# PaxInstrument-T400.net
KiCad netlist of a schematic drawn in EAGLE
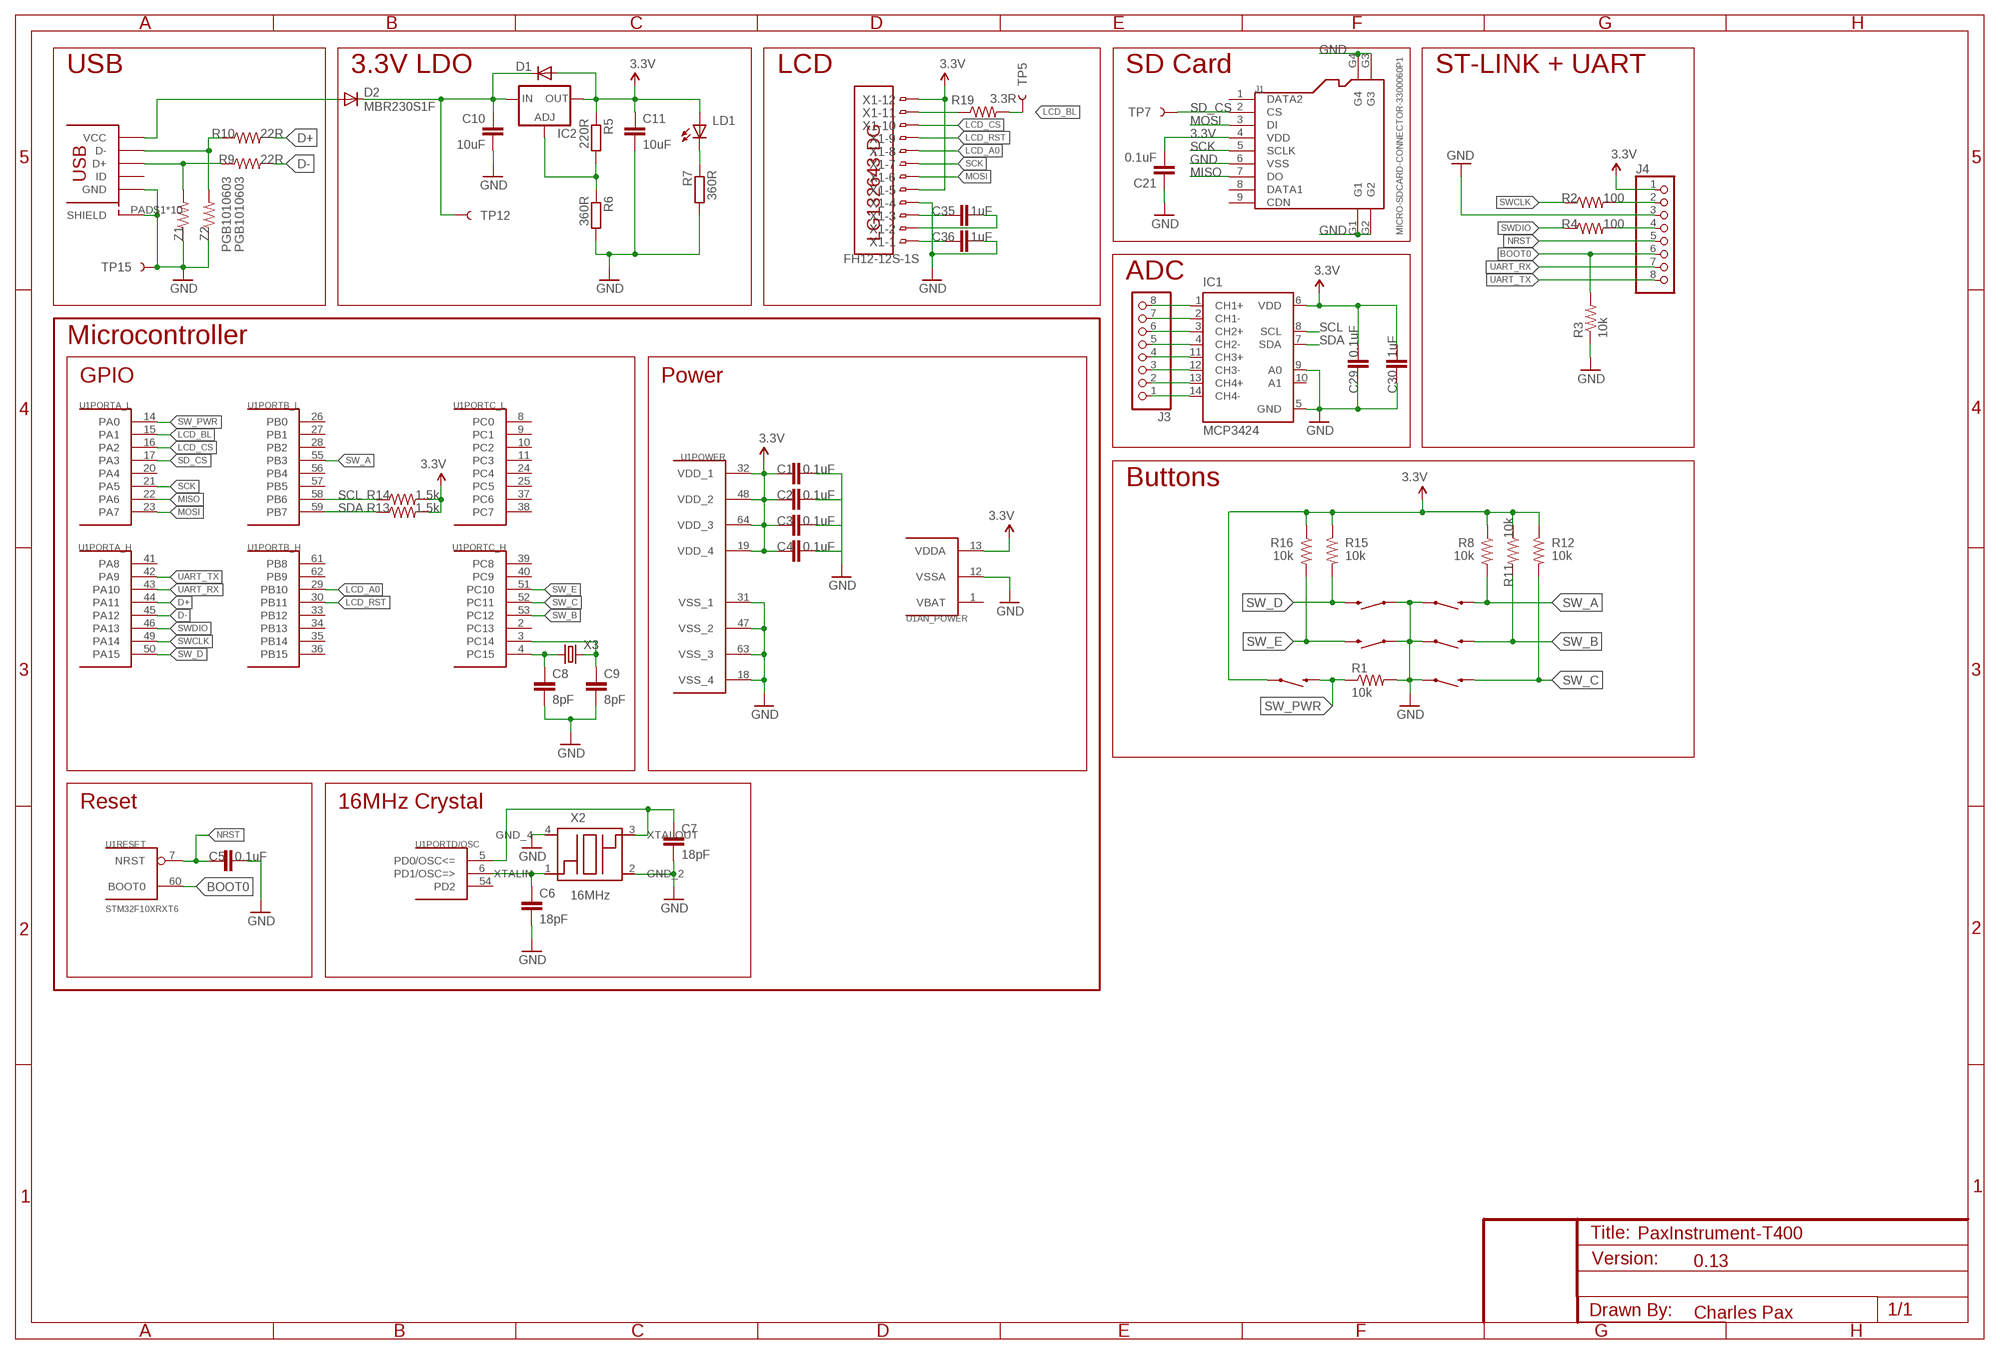
[diagram p0: schematic, sheet 1]

(export (version "E")
  (design (tool "Eeschema 10.0.6"))
  (components
    (comp (ref "C1")
      (value "0.1uF")
      (footprint "eagle-import:SPARKFUN-CAPACITORS_0603-CAP")
      (libsource (lib "eagle-import") (part "SPARKFUN-CAPACITORS_CAP0603-CAP"))
    )
    (comp (ref "C2")
      (value "0.1uF")
      (footprint "eagle-import:SPARKFUN-CAPACITORS_0603-CAP")
      (libsource (lib "eagle-import") (part "SPARKFUN-CAPACITORS_CAP0603-CAP"))
    )
    (comp (ref "C3")
      (value "0.1uF")
      (footprint "eagle-import:SPARKFUN-CAPACITORS_0603-CAP")
      (libsource (lib "eagle-import") (part "SPARKFUN-CAPACITORS_CAP0603-CAP"))
    )
    (comp (ref "C4")
      (value "0.1uF")
      (footprint "eagle-import:SPARKFUN-CAPACITORS_0603-CAP")
      (libsource (lib "eagle-import") (part "SPARKFUN-CAPACITORS_CAP0603-CAP"))
    )
    (comp (ref "C5")
      (value "0.1uF")
      (footprint "eagle-import:SPARKFUN-CAPACITORS_0603-CAP")
      (libsource (lib "eagle-import") (part "SPARKFUN-CAPACITORS_CAP0603-CAP"))
    )
    (comp (ref "C6")
      (value "18pF")
      (footprint "eagle-import:SPARKFUN-CAPACITORS_0603-CAP")
      (libsource (lib "eagle-import") (part "SPARKFUN-CAPACITORS_CAP0603-CAP"))
    )
    (comp (ref "C7")
      (value "18pF")
      (footprint "eagle-import:SPARKFUN-CAPACITORS_0603-CAP")
      (libsource (lib "eagle-import") (part "SPARKFUN-CAPACITORS_CAP0603-CAP"))
    )
    (comp (ref "C8")
      (value "8pF")
      (footprint "eagle-import:SPARKFUN-CAPACITORS_0603-CAP")
      (libsource (lib "eagle-import") (part "SPARKFUN-CAPACITORS_CAP0603-CAP"))
    )
    (comp (ref "C9")
      (value "8pF")
      (footprint "eagle-import:SPARKFUN-CAPACITORS_0603-CAP")
      (libsource (lib "eagle-import") (part "SPARKFUN-CAPACITORS_CAP0603-CAP"))
    )
    (comp (ref "C10")
      (value "10uF")
      (footprint "eagle-import:0603")
      (libsource (lib "eagle-import") (part "C0603"))
    )
    (comp (ref "C11")
      (value "10uF")
      (footprint "eagle-import:0603")
      (libsource (lib "eagle-import") (part "C0603"))
    )
    (comp (ref "C21")
      (value "0.1uF")
      (footprint "eagle-import:SPARKFUN-CAPACITORS_0603-CAP")
      (libsource (lib "eagle-import") (part "SPARKFUN-CAPACITORS_CAP0603-CAP"))
    )
    (comp (ref "C29")
      (value "0.1uF")
      (footprint "eagle-import:SPARKFUN-CAPACITORS_0603-CAP")
      (libsource (lib "eagle-import") (part "SPARKFUN-CAPACITORS_CAP0603-CAP"))
    )
    (comp (ref "C30")
      (value "1uF")
      (footprint "eagle-import:SPARKFUN-CAPACITORS_0603-CAP")
      (libsource (lib "eagle-import") (part "SPARKFUN-CAPACITORS_CAP0603-CAP"))
    )
    (comp (ref "C35")
      (value "1uF")
      (footprint "eagle-import:SPARKFUN-CAPACITORS_0603-CAP")
      (libsource (lib "eagle-import") (part "SPARKFUN-CAPACITORS_CAP0603-CAP"))
    )
    (comp (ref "C36")
      (value "1uF")
      (footprint "eagle-import:SPARKFUN-CAPACITORS_0603-CAP")
      (libsource (lib "eagle-import") (part "SPARKFUN-CAPACITORS_CAP0603-CAP"))
    )
    (comp (ref "D1")
      (value "1N4148W")
      (footprint "eagle-import:SOD-123_MINI-SMA")
      (libsource (lib "eagle-import") (part "CGRM400-G1"))
    )
    (comp (ref "D2")
      (value "MBR230S1F")
      (footprint "eagle-import:SOD123")
      (fields (field (name "MF") "DIODES INC") (field (name "MPN") "MBR230S1F-7"))
      (libsource (lib "eagle-import") (part "SPARKFUN-DISCRETESEMI_DIODESOD123SOD123"))
    )
    (comp (ref "IC1")
      (value "MCP3424")
      (footprint "eagle-import:SO14")
      (fields (field (name "MF") "Microchip Technology") (field (name "MPN") "MCP3424-E/SL"))
      (libsource (lib "eagle-import") (part "MCP3424"))
    )
    (comp (ref "IC2")
      (value "LM317AEMP")
      (footprint "eagle-import:SOT223")
      (libsource (lib "eagle-import") (part "LM317?MSTT3"))
    )
    (comp (ref "J1")
      (value "MICRO-SDCARD-CONNECTOR-3300060P1")
      (footprint "eagle-import:9P-SMD-W-RING")
      (fields (field (name "MF") "SUNTECH") (field (name "MPN") "ST-TF-003A"))
      (libsource (lib "eagle-import") (part "MICRO-SDCARD-CONNECTOR-3300060P1"))
    )
    (comp (ref "J2")
      (value "USB_MICROSMT+THRUHULE")
      (footprint "eagle-import:USB_MICRO_THRUHOLE")
      (fields (field (name "MF") "FCI") (field (name "MPN") "10118194-0001LF"))
      (libsource (lib "eagle-import") (part "USB_MICROSMT+THRUHULE"))
    )
    (comp (ref "J3")
      (value "PINHD-1X8")
      (footprint "eagle-import:1X08")
      (libsource (lib "eagle-import") (part "PINHD-1X8"))
    )
    (comp (ref "J4")
      (value "PINHD-1X8")
      (footprint "eagle-import:1X08")
      (libsource (lib "eagle-import") (part "PINHD-1X8"))
    )
    (comp (ref "LD1")
      (value "LEDCHIPLED_0805")
      (footprint "eagle-import:CHIPLED_0805")
      (libsource (lib "eagle-import") (part "LEDCHIPLED_0805"))
    )
    (comp (ref "R1")
      (value "10k")
      (footprint "eagle-import:SPARKFUN-RESISTORS_0603-RES")
      (libsource (lib "eagle-import") (part "SPARKFUN-RESISTORS_RESISTOR0603-RES"))
    )
    (comp (ref "R2")
      (value "100")
      (footprint "eagle-import:SPARKFUN-RESISTORS_0603-RES")
      (libsource (lib "eagle-import") (part "SPARKFUN-RESISTORS_RESISTOR0603-RES"))
    )
    (comp (ref "R3")
      (value "10k")
      (footprint "eagle-import:SPARKFUN-RESISTORS_0603-RES")
      (libsource (lib "eagle-import") (part "SPARKFUN-RESISTORS_RESISTOR0603-RES"))
    )
    (comp (ref "R4")
      (value "100")
      (footprint "eagle-import:SPARKFUN-RESISTORS_0603-RES")
      (libsource (lib "eagle-import") (part "SPARKFUN-RESISTORS_RESISTOR0603-RES"))
    )
    (comp (ref "R5")
      (value "220R")
      (footprint "eagle-import:0603")
      (libsource (lib "eagle-import") (part "R0603"))
    )
    (comp (ref "R6")
      (value "360R")
      (footprint "eagle-import:0603")
      (libsource (lib "eagle-import") (part "R0603"))
    )
    (comp (ref "R7")
      (value "360R")
      (footprint "eagle-import:0603")
      (libsource (lib "eagle-import") (part "R0603"))
    )
    (comp (ref "R8")
      (value "10k")
      (footprint "eagle-import:SPARKFUN-RESISTORS_0603-RES")
      (libsource (lib "eagle-import") (part "SPARKFUN-RESISTORS_RESISTOR0603-RES"))
    )
    (comp (ref "R9")
      (value "22R")
      (footprint "eagle-import:SPARKFUN-RESISTORS_0603-RES")
      (libsource (lib "eagle-import") (part "SPARKFUN-RESISTORS_RESISTOR0603-RES"))
    )
    (comp (ref "R10")
      (value "22R")
      (footprint "eagle-import:SPARKFUN-RESISTORS_0603-RES")
      (libsource (lib "eagle-import") (part "SPARKFUN-RESISTORS_RESISTOR0603-RES"))
    )
    (comp (ref "R11")
      (value "10k")
      (footprint "eagle-import:SPARKFUN-RESISTORS_0603-RES")
      (libsource (lib "eagle-import") (part "SPARKFUN-RESISTORS_RESISTOR0603-RES"))
    )
    (comp (ref "R12")
      (value "10k")
      (footprint "eagle-import:SPARKFUN-RESISTORS_0603-RES")
      (libsource (lib "eagle-import") (part "SPARKFUN-RESISTORS_RESISTOR0603-RES"))
    )
    (comp (ref "R13")
      (value "1.5k")
      (footprint "eagle-import:SPARKFUN-RESISTORS_0603-RES")
      (libsource (lib "eagle-import") (part "SPARKFUN-RESISTORS_RESISTOR0603-RES"))
    )
    (comp (ref "R14")
      (value "1.5k")
      (footprint "eagle-import:SPARKFUN-RESISTORS_0603-RES")
      (libsource (lib "eagle-import") (part "SPARKFUN-RESISTORS_RESISTOR0603-RES"))
    )
    (comp (ref "R15")
      (value "10k")
      (footprint "eagle-import:SPARKFUN-RESISTORS_0603-RES")
      (libsource (lib "eagle-import") (part "SPARKFUN-RESISTORS_RESISTOR0603-RES"))
    )
    (comp (ref "R16")
      (value "10k")
      (footprint "eagle-import:SPARKFUN-RESISTORS_0603-RES")
      (libsource (lib "eagle-import") (part "SPARKFUN-RESISTORS_RESISTOR0603-RES"))
    )
    (comp (ref "R19")
      (value "3.3R")
      (footprint "eagle-import:SPARKFUN-RESISTORS_0603-RES")
      (libsource (lib "eagle-import") (part "SPARKFUN-RESISTORS_RESISTOR0603-RES"))
    )
    (comp (ref "S1")
      (value "SWITCH-MOMENTARY-2SMD")
      (footprint "eagle-import:TACTILE_SWITCH_SMD")
      (fields (field (name "MF") "C&K Components") (field (name "MPN") "RS-187R05A2-DS MT RT"))
      (libsource (lib "eagle-import") (part "SWITCH-MOMENTARY-2SMD"))
    )
    (comp (ref "S2")
      (value "SWITCH-MOMENTARY-2SMD")
      (footprint "eagle-import:TACTILE_SWITCH_SMD")
      (fields (field (name "MF") "C&K Components") (field (name "MPN") "RS-187R05A2-DS MT RT"))
      (libsource (lib "eagle-import") (part "SWITCH-MOMENTARY-2SMD"))
    )
    (comp (ref "S3")
      (value "SWITCH-MOMENTARY-2SMD")
      (footprint "eagle-import:TACTILE_SWITCH_SMD")
      (fields (field (name "MF") "C&K Components") (field (name "MPN") "RS-187R05A2-DS MT RT"))
      (libsource (lib "eagle-import") (part "SWITCH-MOMENTARY-2SMD"))
    )
    (comp (ref "S4")
      (value "SWITCH-MOMENTARY-2SMD")
      (footprint "eagle-import:TACTILE_SWITCH_SMD")
      (fields (field (name "MF") "C&K Components") (field (name "MPN") "RS-187R05A2-DS MT RT"))
      (libsource (lib "eagle-import") (part "SWITCH-MOMENTARY-2SMD"))
    )
    (comp (ref "S5")
      (value "SWITCH-MOMENTARY-2SMD")
      (footprint "eagle-import:TACTILE_SWITCH_SMD")
      (fields (field (name "MF") "C&K Components") (field (name "MPN") "RS-187R05A2-DS MT RT"))
      (libsource (lib "eagle-import") (part "SWITCH-MOMENTARY-2SMD"))
    )
    (comp (ref "S6")
      (value "SWITCH-MOMENTARY-2SMD")
      (footprint "eagle-import:TACTILE_SWITCH_SMD")
      (fields (field (name "MF") "C&K Components") (field (name "MPN") "RS-187R05A2-DS MT RT"))
      (libsource (lib "eagle-import") (part "SWITCH-MOMENTARY-2SMD"))
    )
    (comp (ref "TP5")
      (value "LCD_BL")
      (footprint "eagle-import:TP_15TH")
      (libsource (lib "eagle-import") (part "TEST-POINTTP_15TH_THRU"))
    )
    (comp (ref "TP7")
      (value "SD_CS")
      (footprint "eagle-import:TP_15TH")
      (libsource (lib "eagle-import") (part "TEST-POINTTP_15TH_THRU"))
    )
    (comp (ref "TP12")
      (value "VBUS")
      (footprint "eagle-import:TP_15TH")
      (libsource (lib "eagle-import") (part "TEST-POINTTP_15TH_THRU"))
    )
    (comp (ref "TP15")
      (value "GND")
      (footprint "eagle-import:TP_15TH")
      (libsource (lib "eagle-import") (part "TEST-POINTTP_15TH_THRU"))
    )
    (comp (ref "U$5")
      (value "LG132643-DG")
      (footprint "eagle-import:LG132643-DG")
      (fields (field (name "MPN") "LG132643-DW"))
      (libsource (lib "eagle-import") (part "LG132643-DG"))
    )
    (comp (ref "U1")
      (value "STM32F10XRXT6")
      (footprint "eagle-import:TQFP64")
      (libsource (lib "eagle-import") (part "STM32F10XRXT6"))
    )
    (comp (ref "X1")
      (value "FH12-12S-1S")
      (footprint "eagle-import:FH12-12S-1SH")
      (fields (field (name "MF") "Hirose Connector") (field (name "MPN") "FH12-12S-1SH(55)"))
      (libsource (lib "eagle-import") (part "FH12-12S-1S"))
    )
    (comp (ref "X2")
      (value "16MHz")
      (footprint "eagle-import:FA-238")
      (libsource (lib "eagle-import") (part "FA-238"))
    )
    (comp (ref "X3")
      (value "CRYSTALTC26H")
      (footprint "eagle-import:TC26H")
      (libsource (lib "eagle-import") (part "CRYSTALTC26H"))
    )
    (comp (ref "Z1")
      (value "PGB1010603")
      (footprint "eagle-import:SPARKFUN-RESISTORS_0603-RES")
      (fields (field (name "MF") "Littelfuse") (field (name "MPN") "PGB1010603NRHF"))
      (libsource (lib "eagle-import") (part "SPARKFUN-RESISTORS_RESISTOR0603-RES"))
    )
    (comp (ref "Z2")
      (value "PGB1010603")
      (footprint "eagle-import:SPARKFUN-RESISTORS_0603-RES")
      (fields (field (name "MF") "Littelfuse") (field (name "MPN") "PGB1010603NRHF"))
      (libsource (lib "eagle-import") (part "SPARKFUN-RESISTORS_RESISTOR0603-RES"))
    )
  )
  (nets
    (net (code "1") (name "/SCL") (class "Default")
      (node (ref "IC1") (pin "8") (pinfunction "SCL_8") (pintype "input"))
      (node (ref "R14") (pin "1") (pinfunction "1_1") (pintype "passive"))
      (node (ref "U1") (pin "58") (pinfunction "PB6_58") (pintype "bidirectional"))
    )
    (net (code "2") (name "/SDA") (class "Default")
      (node (ref "IC1") (pin "7") (pinfunction "SDA_7") (pintype "bidirectional"))
      (node (ref "R13") (pin "1") (pinfunction "1_1") (pintype "passive"))
      (node (ref "U1") (pin "59") (pinfunction "PB7_59") (pintype "bidirectional"))
    )
    (net (code "3") (name "/VBAT") (class "Default")
      (node (ref "U1") (pin "1") (pinfunction "VBAT_1") (pintype "power_in"))
    )
    (net (code "4") (name "3.3V") (class "Default")
      (node (ref "C1") (pin "1") (pinfunction "1_1") (pintype "passive"))
      (node (ref "C11") (pin "1") (pinfunction "1_1") (pintype "passive"))
      (node (ref "C2") (pin "1") (pinfunction "1_1") (pintype "passive"))
      (node (ref "C21") (pin "2") (pinfunction "2_2") (pintype "passive"))
      (node (ref "C29") (pin "1") (pinfunction "1_1") (pintype "passive"))
      (node (ref "C3") (pin "1") (pinfunction "1_1") (pintype "passive"))
      (node (ref "C30") (pin "1") (pinfunction "1_1") (pintype "passive"))
      (node (ref "C4") (pin "1") (pinfunction "1_1") (pintype "passive"))
      (node (ref "D1") (pin "A") (pinfunction "A_A") (pintype "passive"))
      (node (ref "IC1") (pin "6") (pinfunction "VDD_6") (pintype "power_in"))
      (node (ref "IC2") (pin "2") (pinfunction "OUT_2") (pintype "passive"))
      (node (ref "IC2") (pin "4") (pinfunction "OUT_4") (pintype "passive"))
      (node (ref "J1") (pin "4") (pinfunction "VDD_4") (pintype "bidirectional"))
      (node (ref "J4") (pin "1") (pinfunction "1_1") (pintype "passive"))
      (node (ref "LD1") (pin "A") (pinfunction "A_A") (pintype "passive"))
      (node (ref "R11") (pin "1") (pinfunction "1_1") (pintype "passive"))
      (node (ref "R12") (pin "1") (pinfunction "1_1") (pintype "passive"))
      (node (ref "R13") (pin "2") (pinfunction "2_2") (pintype "passive"))
      (node (ref "R14") (pin "2") (pinfunction "2_2") (pintype "passive"))
      (node (ref "R15") (pin "1") (pinfunction "1_1") (pintype "passive"))
      (node (ref "R16") (pin "1") (pinfunction "1_1") (pintype "passive"))
      (node (ref "R5") (pin "1") (pinfunction "1_1") (pintype "passive"))
      (node (ref "R8") (pin "1") (pinfunction "1_1") (pintype "passive"))
      (node (ref "S6") (pin "1") (pinfunction "1_1") (pintype "passive"))
      (node (ref "U1") (pin "13") (pinfunction "VDDA_13") (pintype "power_in"))
      (node (ref "U1") (pin "19") (pinfunction "VDD_4_19") (pintype "power_in"))
      (node (ref "U1") (pin "32") (pinfunction "VDD_1_32") (pintype "power_in"))
      (node (ref "U1") (pin "48") (pinfunction "VDD_2_48") (pintype "power_in"))
      (node (ref "U1") (pin "64") (pinfunction "VDD_3_64") (pintype "power_in"))
      (node (ref "X1") (pin "12") (pinfunction "1_12") (pintype "passive"))
      (node (ref "X1") (pin "5") (pinfunction "1_5") (pintype "passive"))
    )
    (net (code "5") (name "BOOT0") (class "Default")
      (node (ref "J4") (pin "6") (pinfunction "6_6") (pintype "passive"))
      (node (ref "R3") (pin "2") (pinfunction "2_2") (pintype "passive"))
      (node (ref "U1") (pin "60") (pinfunction "BOOT0_60") (pintype "input"))
    )
    (net (code "6") (name "D+") (class "Default")
      (node (ref "R10") (pin "2") (pinfunction "2_2") (pintype "passive"))
      (node (ref "U1") (pin "44") (pinfunction "PA11_44") (pintype "bidirectional"))
    )
    (net (code "7") (name "D-") (class "Default")
      (node (ref "R9") (pin "2") (pinfunction "2_2") (pintype "passive"))
      (node (ref "U1") (pin "45") (pinfunction "PA12_45") (pintype "bidirectional"))
    )
    (net (code "8") (name "GND") (class "Default")
      (node (ref "C1") (pin "2") (pinfunction "2_2") (pintype "passive"))
      (node (ref "C10") (pin "2") (pinfunction "2_2") (pintype "passive"))
      (node (ref "C11") (pin "2") (pinfunction "2_2") (pintype "passive"))
      (node (ref "C21") (pin "1") (pinfunction "1_1") (pintype "passive"))
      (node (ref "C29") (pin "2") (pinfunction "2_2") (pintype "passive"))
      (node (ref "C30") (pin "2") (pinfunction "2_2") (pintype "passive"))
      (node (ref "C36") (pin "1") (pinfunction "1_1") (pintype "passive"))
      (node (ref "C5") (pin "2") (pinfunction "2_2") (pintype "passive"))
      (node (ref "C6") (pin "2") (pinfunction "2_2") (pintype "passive"))
      (node (ref "C7") (pin "2") (pinfunction "2_2") (pintype "passive"))
      (node (ref "C8") (pin "2") (pinfunction "2_2") (pintype "passive"))
      (node (ref "C9") (pin "2") (pinfunction "2_2") (pintype "passive"))
      (node (ref "IC1") (pin "5") (pinfunction "GND_5") (pintype "power_in"))
      (node (ref "IC1") (pin "9") (pinfunction "A0_9") (pintype "input"))
      (node (ref "J1") (pin "6") (pinfunction "VSS_6") (pintype "bidirectional"))
      (node (ref "J1") (pin "G1") (pinfunction "G1_G1") (pintype "bidirectional"))
      (node (ref "J1") (pin "G2") (pinfunction "G2_G2") (pintype "bidirectional"))
      (node (ref "J1") (pin "G3") (pinfunction "G3_G3") (pintype "bidirectional"))
      (node (ref "J1") (pin "G4") (pinfunction "G4_G4") (pintype "bidirectional"))
      (node (ref "J2") (pin "PAD$1") (pinfunction "SHIELD_PAD$1") (pintype "bidirectional"))
      (node (ref "J2") (pin "PAD$10") (pinfunction "SHIELD_PAD$10") (pintype "bidirectional"))
      (node (ref "J2") (pin "PAD$2") (pinfunction "SHIELD_PAD$2") (pintype "bidirectional"))
      (node (ref "J2") (pin "PAD$3") (pinfunction "SHIELD_PAD$3") (pintype "bidirectional"))
      (node (ref "J2") (pin "PAD$4") (pinfunction "SHIELD_PAD$4") (pintype "bidirectional"))
      (node (ref "J2") (pin "PAD$5") (pinfunction "SHIELD_PAD$5") (pintype "bidirectional"))
      (node (ref "J2") (pin "PAD$6") (pinfunction "SHIELD_PAD$6") (pintype "bidirectional"))
      (node (ref "J2") (pin "PAD$7") (pinfunction "SHIELD_PAD$7") (pintype "bidirectional"))
      (node (ref "J2") (pin "PAD$8") (pinfunction "SHIELD_PAD$8") (pintype "bidirectional"))
      (node (ref "J2") (pin "PAD$9") (pinfunction "SHIELD_PAD$9") (pintype "bidirectional"))
      (node (ref "J2") (pin "PIN$5") (pinfunction "GND_PIN$5") (pintype "bidirectional"))
      (node (ref "J4") (pin "3") (pinfunction "3_3") (pintype "passive"))
      (node (ref "R1") (pin "2") (pinfunction "2_2") (pintype "passive"))
      (node (ref "R3") (pin "1") (pinfunction "1_1") (pintype "passive"))
      (node (ref "R6") (pin "2") (pinfunction "2_2") (pintype "passive"))
      (node (ref "R7") (pin "2") (pinfunction "2_2") (pintype "passive"))
      (node (ref "S1") (pin "1") (pinfunction "1_1") (pintype "passive"))
      (node (ref "S2") (pin "1") (pinfunction "1_1") (pintype "passive"))
      (node (ref "S3") (pin "1") (pinfunction "1_1") (pintype "passive"))
      (node (ref "S4") (pin "1") (pinfunction "1_1") (pintype "passive"))
      (node (ref "S5") (pin "1") (pinfunction "1_1") (pintype "passive"))
      (node (ref "TP15") (pin "P$1") (pinfunction "1_P$1") (pintype "bidirectional"))
      (node (ref "U1") (pin "12") (pinfunction "VSSA_12") (pintype "power_in"))
      (node (ref "U1") (pin "18") (pinfunction "VSS_4_18") (pintype "power_in"))
      (node (ref "U1") (pin "31") (pinfunction "VSS_1_31") (pintype "power_in"))
      (node (ref "U1") (pin "47") (pinfunction "VSS_2_47") (pintype "power_in"))
      (node (ref "U1") (pin "63") (pinfunction "VSS_3_63") (pintype "power_in"))
      (node (ref "X1") (pin "4") (pinfunction "1_4") (pintype "passive"))
      (node (ref "X2") (pin "2") (pinfunction "GND_2_2") (pintype "bidirectional"))
      (node (ref "X2") (pin "4") (pinfunction "GND_4_4") (pintype "bidirectional"))
      (node (ref "Z1") (pin "1") (pinfunction "1_1") (pintype "passive"))
      (node (ref "Z2") (pin "1") (pinfunction "1_1") (pintype "passive"))
    )
    (net (code "9") (name "LCD_A0") (class "Default")
      (node (ref "U1") (pin "29") (pinfunction "PB10_29") (pintype "bidirectional"))
      (node (ref "X1") (pin "8") (pinfunction "1_8") (pintype "passive"))
    )
    (net (code "10") (name "LCD_BL") (class "Default")
      (node (ref "R19") (pin "2") (pinfunction "2_2") (pintype "passive"))
      (node (ref "TP5") (pin "P$1") (pinfunction "1_P$1") (pintype "bidirectional"))
      (node (ref "U1") (pin "15") (pinfunction "PA1_15") (pintype "bidirectional"))
    )
    (net (code "11") (name "LCD_CS") (class "Default")
      (node (ref "U1") (pin "16") (pinfunction "PA2_16") (pintype "bidirectional"))
      (node (ref "X1") (pin "10") (pinfunction "1_10") (pintype "passive"))
    )
    (net (code "12") (name "LCD_RST") (class "Default")
      (node (ref "U1") (pin "30") (pinfunction "PB11_30") (pintype "bidirectional"))
      (node (ref "X1") (pin "9") (pinfunction "1_9") (pintype "passive"))
    )
    (net (code "13") (name "MISO") (class "Default")
      (node (ref "J1") (pin "7") (pinfunction "DO_7") (pintype "bidirectional"))
      (node (ref "U1") (pin "22") (pinfunction "PA6_22") (pintype "bidirectional"))
    )
    (net (code "14") (name "MOSI") (class "Default")
      (node (ref "J1") (pin "3") (pinfunction "DI_3") (pintype "bidirectional"))
      (node (ref "U1") (pin "23") (pinfunction "PA7_23") (pintype "bidirectional"))
      (node (ref "X1") (pin "6") (pinfunction "1_6") (pintype "passive"))
    )
    (net (code "15") (name "NRST") (class "Default")
      (node (ref "C5") (pin "1") (pinfunction "1_1") (pintype "passive"))
      (node (ref "J4") (pin "5") (pinfunction "5_5") (pintype "passive"))
      (node (ref "U1") (pin "7") (pinfunction "NRST_7") (pintype "input"))
    )
    (net (code "16") (name "Net-(C36-Pad2)") (class "Default")
      (node (ref "C36") (pin "2") (pinfunction "2_2") (pintype "passive"))
      (node (ref "X1") (pin "1") (pinfunction "1_1") (pintype "passive"))
    )
    (net (code "17") (name "Net-(IC1-CH1+)") (class "Default")
      (node (ref "IC1") (pin "1") (pinfunction "CH1+_1") (pintype "input"))
      (node (ref "J3") (pin "8") (pinfunction "8_8") (pintype "passive"))
    )
    (net (code "18") (name "Net-(IC1-CH1-)") (class "Default")
      (node (ref "IC1") (pin "2") (pinfunction "CH1-_2") (pintype "input"))
      (node (ref "J3") (pin "7") (pinfunction "7_7") (pintype "passive"))
    )
    (net (code "19") (name "Net-(IC1-CH2+)") (class "Default")
      (node (ref "IC1") (pin "3") (pinfunction "CH2+_3") (pintype "input"))
      (node (ref "J3") (pin "6") (pinfunction "6_6") (pintype "passive"))
    )
    (net (code "20") (name "Net-(IC1-CH2-)") (class "Default")
      (node (ref "IC1") (pin "4") (pinfunction "CH2-_4") (pintype "input"))
      (node (ref "J3") (pin "5") (pinfunction "5_5") (pintype "passive"))
    )
    (net (code "21") (name "Net-(IC1-CH3+)") (class "Default")
      (node (ref "IC1") (pin "11") (pinfunction "CH3+_11") (pintype "input"))
      (node (ref "J3") (pin "4") (pinfunction "4_4") (pintype "passive"))
    )
    (net (code "22") (name "Net-(IC1-CH3-)") (class "Default")
      (node (ref "IC1") (pin "12") (pinfunction "CH3-_12") (pintype "input"))
      (node (ref "J3") (pin "3") (pinfunction "3_3") (pintype "passive"))
    )
    (net (code "23") (name "Net-(IC1-CH4+)") (class "Default")
      (node (ref "IC1") (pin "13") (pinfunction "CH4+_13") (pintype "input"))
      (node (ref "J3") (pin "2") (pinfunction "2_2") (pintype "passive"))
    )
    (net (code "24") (name "Net-(IC1-CH4-)") (class "Default")
      (node (ref "IC1") (pin "14") (pinfunction "CH4-_14") (pintype "input"))
      (node (ref "J3") (pin "1") (pinfunction "1_1") (pintype "passive"))
    )
    (net (code "25") (name "Net-(IC2-ADJ)") (class "Default")
      (node (ref "IC2") (pin "1") (pinfunction "ADJ_1") (pintype "input"))
      (node (ref "R5") (pin "2") (pinfunction "2_2") (pintype "passive"))
      (node (ref "R6") (pin "1") (pinfunction "1_1") (pintype "passive"))
    )
    (net (code "26") (name "Net-(IC2-IN)") (class "Default")
      (node (ref "C10") (pin "1") (pinfunction "1_1") (pintype "passive"))
      (node (ref "D1") (pin "C") (pinfunction "C_C") (pintype "passive"))
      (node (ref "D2") (pin "C") (pinfunction "C_C") (pintype "passive"))
      (node (ref "IC2") (pin "3") (pinfunction "IN_3") (pintype "input"))
      (node (ref "TP12") (pin "P$1") (pinfunction "1_P$1") (pintype "bidirectional"))
    )
    (net (code "27") (name "Net-(J2-D+)") (class "Default")
      (node (ref "J2") (pin "PIN$3") (pinfunction "D+_PIN$3") (pintype "bidirectional"))
      (node (ref "R9") (pin "1") (pinfunction "1_1") (pintype "passive"))
      (node (ref "Z1") (pin "2") (pinfunction "2_2") (pintype "passive"))
    )
    (net (code "28") (name "Net-(J2-D-)") (class "Default")
      (node (ref "J2") (pin "PIN$2") (pinfunction "D-_PIN$2") (pintype "bidirectional"))
      (node (ref "R10") (pin "1") (pinfunction "1_1") (pintype "passive"))
      (node (ref "Z2") (pin "2") (pinfunction "2_2") (pintype "passive"))
    )
    (net (code "29") (name "Net-(J2-VCC)") (class "Default")
      (node (ref "D2") (pin "A") (pinfunction "A_A") (pintype "passive"))
      (node (ref "J2") (pin "PIN$1") (pinfunction "VCC_PIN$1") (pintype "bidirectional"))
    )
    (net (code "30") (name "Net-(J4-Pad2)") (class "Default")
      (node (ref "J4") (pin "2") (pinfunction "2_2") (pintype "passive"))
      (node (ref "R2") (pin "2") (pinfunction "2_2") (pintype "passive"))
    )
    (net (code "31") (name "Net-(J4-Pad4)") (class "Default")
      (node (ref "J4") (pin "4") (pinfunction "4_4") (pintype "passive"))
      (node (ref "R4") (pin "2") (pinfunction "2_2") (pintype "passive"))
    )
    (net (code "32") (name "Net-(LD1-PadC)") (class "Default")
      (node (ref "LD1") (pin "C") (pinfunction "C_C") (pintype "passive"))
      (node (ref "R7") (pin "1") (pinfunction "1_1") (pintype "passive"))
    )
    (net (code "33") (name "Net-(U1F-PC14)") (class "Default")
      (node (ref "C9") (pin "1") (pinfunction "1_1") (pintype "passive"))
      (node (ref "U1") (pin "3") (pinfunction "PC14_3") (pintype "bidirectional"))
      (node (ref "X3") (pin "2") (pinfunction "2_2") (pintype "passive"))
    )
    (net (code "34") (name "Net-(U1F-PC15)") (class "Default")
      (node (ref "C8") (pin "1") (pinfunction "1_1") (pintype "passive"))
      (node (ref "U1") (pin "4") (pinfunction "PC15_4") (pintype "bidirectional"))
      (node (ref "X3") (pin "1") (pinfunction "1_1") (pintype "passive"))
    )
    (net (code "35") (name "Net-(U1H-PD0{slash}OSC<=)") (class "Default")
      (node (ref "C7") (pin "1") (pinfunction "1_1") (pintype "passive"))
      (node (ref "U1") (pin "5") (pinfunction "PD0/OSC<=_5") (pintype "bidirectional"))
      (node (ref "X2") (pin "3") (pinfunction "XTALOUT_3") (pintype "bidirectional"))
    )
    (net (code "36") (name "Net-(U1H-PD1{slash}OSC=>)") (class "Default")
      (node (ref "C6") (pin "1") (pinfunction "1_1") (pintype "passive"))
      (node (ref "U1") (pin "6") (pinfunction "PD1/OSC=>_6") (pintype "bidirectional"))
      (node (ref "X2") (pin "1") (pinfunction "XTALIN_1") (pintype "bidirectional"))
    )
    (net (code "37") (name "Net-(X1C-1)") (class "Default")
      (node (ref "R19") (pin "1") (pinfunction "1_1") (pintype "passive"))
      (node (ref "X1") (pin "11") (pinfunction "1_11") (pintype "passive"))
    )
    (net (code "38") (name "Net-(X1E-1)") (class "Default")
      (node (ref "C35") (pin "2") (pinfunction "2_2") (pintype "passive"))
      (node (ref "X1") (pin "2") (pinfunction "1_2") (pintype "passive"))
    )
    (net (code "39") (name "Net-(X1F-1)") (class "Default")
      (node (ref "C35") (pin "1") (pinfunction "1_1") (pintype "passive"))
      (node (ref "X1") (pin "3") (pinfunction "1_3") (pintype "passive"))
    )
    (net (code "40") (name "SCK") (class "Default")
      (node (ref "J1") (pin "5") (pinfunction "SCLK_5") (pintype "bidirectional"))
      (node (ref "U1") (pin "21") (pinfunction "PA5_21") (pintype "bidirectional"))
      (node (ref "X1") (pin "7") (pinfunction "1_7") (pintype "passive"))
    )
    (net (code "41") (name "SD_CS") (class "Default")
      (node (ref "J1") (pin "2") (pinfunction "CS_2") (pintype "bidirectional"))
      (node (ref "TP7") (pin "P$1") (pinfunction "1_P$1") (pintype "bidirectional"))
      (node (ref "U1") (pin "17") (pinfunction "PA3_17") (pintype "bidirectional"))
    )
    (net (code "42") (name "SWCLK") (class "Default")
      (node (ref "R2") (pin "1") (pinfunction "1_1") (pintype "passive"))
      (node (ref "U1") (pin "49") (pinfunction "PA14_49") (pintype "bidirectional"))
    )
    (net (code "43") (name "SWDIO") (class "Default")
      (node (ref "R4") (pin "1") (pinfunction "1_1") (pintype "passive"))
      (node (ref "U1") (pin "46") (pinfunction "PA13_46") (pintype "bidirectional"))
    )
    (net (code "44") (name "SW_A") (class "Default")
      (node (ref "R8") (pin "2") (pinfunction "2_2") (pintype "passive"))
      (node (ref "S3") (pin "3") (pinfunction "2_3") (pintype "passive"))
      (node (ref "U1") (pin "55") (pinfunction "PB3_55") (pintype "bidirectional"))
    )
    (net (code "45") (name "SW_B") (class "Default")
      (node (ref "R11") (pin "2") (pinfunction "2_2") (pintype "passive"))
      (node (ref "S2") (pin "3") (pinfunction "2_3") (pintype "passive"))
      (node (ref "U1") (pin "53") (pinfunction "PC12_53") (pintype "bidirectional"))
    )
    (net (code "46") (name "SW_C") (class "Default")
      (node (ref "R12") (pin "2") (pinfunction "2_2") (pintype "passive"))
      (node (ref "S1") (pin "3") (pinfunction "2_3") (pintype "passive"))
      (node (ref "U1") (pin "52") (pinfunction "PC11_52") (pintype "bidirectional"))
    )
    (net (code "47") (name "SW_D") (class "Default")
      (node (ref "R15") (pin "2") (pinfunction "2_2") (pintype "passive"))
      (node (ref "S4") (pin "3") (pinfunction "2_3") (pintype "passive"))
      (node (ref "U1") (pin "50") (pinfunction "PA15_50") (pintype "bidirectional"))
    )
    (net (code "48") (name "SW_E") (class "Default")
      (node (ref "R16") (pin "2") (pinfunction "2_2") (pintype "passive"))
      (node (ref "S5") (pin "3") (pinfunction "2_3") (pintype "passive"))
      (node (ref "U1") (pin "51") (pinfunction "PC10_51") (pintype "bidirectional"))
    )
    (net (code "49") (name "SW_PWR") (class "Default")
      (node (ref "R1") (pin "1") (pinfunction "1_1") (pintype "passive"))
      (node (ref "S6") (pin "3") (pinfunction "2_3") (pintype "passive"))
      (node (ref "U1") (pin "14") (pinfunction "PA0_14") (pintype "bidirectional"))
    )
    (net (code "50") (name "UART_RX") (class "Default")
      (node (ref "J4") (pin "7") (pinfunction "7_7") (pintype "passive"))
      (node (ref "U1") (pin "43") (pinfunction "PA10_43") (pintype "bidirectional"))
    )
    (net (code "51") (name "UART_TX") (class "Default")
      (node (ref "J4") (pin "8") (pinfunction "8_8") (pintype "passive"))
      (node (ref "U1") (pin "42") (pinfunction "PA9_42") (pintype "bidirectional"))
    )
    (net (code "52") (name "unconnected-(C2-Pad2)") (class "Default")
      (node (ref "C2") (pin "2") (pinfunction "2_2") (pintype "passive"))
    )
    (net (code "53") (name "unconnected-(C3-Pad2)") (class "Default")
      (node (ref "C3") (pin "2") (pinfunction "2_2") (pintype "passive"))
    )
    (net (code "54") (name "unconnected-(C4-Pad2)") (class "Default")
      (node (ref "C4") (pin "2") (pinfunction "2_2") (pintype "passive"))
    )
    (net (code "55") (name "unconnected-(IC1-A1-Pad10)") (class "Default")
      (node (ref "IC1") (pin "10") (pinfunction "A1_10") (pintype "input"))
    )
    (net (code "56") (name "unconnected-(J1-CDN-Pad9)") (class "Default")
      (node (ref "J1") (pin "9") (pinfunction "CDN_9") (pintype "bidirectional"))
    )
    (net (code "57") (name "unconnected-(J1-DATA1-Pad8)") (class "Default")
      (node (ref "J1") (pin "8") (pinfunction "DATA1_8") (pintype "bidirectional"))
    )
    (net (code "58") (name "unconnected-(J1-DATA2-Pad1)") (class "Default")
      (node (ref "J1") (pin "1") (pinfunction "DATA2_1") (pintype "bidirectional"))
    )
    (net (code "59") (name "unconnected-(J2-ID-PadPIN$4)") (class "Default")
      (node (ref "J2") (pin "PIN$4") (pinfunction "ID_PIN$4") (pintype "bidirectional"))
    )
    (net (code "60") (name "unconnected-(U1B-PA8-Pad41)") (class "Default")
      (node (ref "U1") (pin "41") (pinfunction "PA8_41") (pintype "bidirectional"))
    )
    (net (code "61") (name "unconnected-(U1C-PA4-Pad20)") (class "Default")
      (node (ref "U1") (pin "20") (pinfunction "PA4_20") (pintype "bidirectional"))
    )
    (net (code "62") (name "unconnected-(U1D-PB8-Pad61)") (class "Default")
      (node (ref "U1") (pin "61") (pinfunction "PB8_61") (pintype "bidirectional"))
    )
    (net (code "63") (name "unconnected-(U1D-PB9-Pad62)") (class "Default")
      (node (ref "U1") (pin "62") (pinfunction "PB9_62") (pintype "bidirectional"))
    )
    (net (code "64") (name "unconnected-(U1D-PB12-Pad33)") (class "Default")
      (node (ref "U1") (pin "33") (pinfunction "PB12_33") (pintype "bidirectional"))
    )
    (net (code "65") (name "unconnected-(U1D-PB13-Pad34)") (class "Default")
      (node (ref "U1") (pin "34") (pinfunction "PB13_34") (pintype "bidirectional"))
    )
    (net (code "66") (name "unconnected-(U1D-PB14-Pad35)") (class "Default")
      (node (ref "U1") (pin "35") (pinfunction "PB14_35") (pintype "bidirectional"))
    )
    (net (code "67") (name "unconnected-(U1D-PB15-Pad36)") (class "Default")
      (node (ref "U1") (pin "36") (pinfunction "PB15_36") (pintype "bidirectional"))
    )
    (net (code "68") (name "unconnected-(U1E-PB0-Pad26)") (class "Default")
      (node (ref "U1") (pin "26") (pinfunction "PB0_26") (pintype "bidirectional"))
    )
    (net (code "69") (name "unconnected-(U1E-PB1-Pad27)") (class "Default")
      (node (ref "U1") (pin "27") (pinfunction "PB1_27") (pintype "bidirectional"))
    )
    (net (code "70") (name "unconnected-(U1E-PB2-Pad28)") (class "Default")
      (node (ref "U1") (pin "28") (pinfunction "PB2_28") (pintype "bidirectional"))
    )
    (net (code "71") (name "unconnected-(U1E-PB4-Pad56)") (class "Default")
      (node (ref "U1") (pin "56") (pinfunction "PB4_56") (pintype "bidirectional"))
    )
    (net (code "72") (name "unconnected-(U1E-PB5-Pad57)") (class "Default")
      (node (ref "U1") (pin "57") (pinfunction "PB5_57") (pintype "bidirectional"))
    )
    (net (code "73") (name "unconnected-(U1F-PC8-Pad39)") (class "Default")
      (node (ref "U1") (pin "39") (pinfunction "PC8_39") (pintype "bidirectional"))
    )
    (net (code "74") (name "unconnected-(U1F-PC9-Pad40)") (class "Default")
      (node (ref "U1") (pin "40") (pinfunction "PC9_40") (pintype "bidirectional"))
    )
    (net (code "75") (name "unconnected-(U1F-PC13-Pad2)") (class "Default")
      (node (ref "U1") (pin "2") (pinfunction "PC13_2") (pintype "bidirectional"))
    )
    (net (code "76") (name "unconnected-(U1G-PC0-Pad8)") (class "Default")
      (node (ref "U1") (pin "8") (pinfunction "PC0_8") (pintype "bidirectional"))
    )
    (net (code "77") (name "unconnected-(U1G-PC1-Pad9)") (class "Default")
      (node (ref "U1") (pin "9") (pinfunction "PC1_9") (pintype "bidirectional"))
    )
    (net (code "78") (name "unconnected-(U1G-PC2-Pad10)") (class "Default")
      (node (ref "U1") (pin "10") (pinfunction "PC2_10") (pintype "bidirectional"))
    )
    (net (code "79") (name "unconnected-(U1G-PC3-Pad11)") (class "Default")
      (node (ref "U1") (pin "11") (pinfunction "PC3_11") (pintype "bidirectional"))
    )
    (net (code "80") (name "unconnected-(U1G-PC4-Pad24)") (class "Default")
      (node (ref "U1") (pin "24") (pinfunction "PC4_24") (pintype "bidirectional"))
    )
    (net (code "81") (name "unconnected-(U1G-PC5-Pad25)") (class "Default")
      (node (ref "U1") (pin "25") (pinfunction "PC5_25") (pintype "bidirectional"))
    )
    (net (code "82") (name "unconnected-(U1G-PC6-Pad37)") (class "Default")
      (node (ref "U1") (pin "37") (pinfunction "PC6_37") (pintype "bidirectional"))
    )
    (net (code "83") (name "unconnected-(U1G-PC7-Pad38)") (class "Default")
      (node (ref "U1") (pin "38") (pinfunction "PC7_38") (pintype "bidirectional"))
    )
    (net (code "84") (name "unconnected-(U1H-PD2-Pad54)") (class "Default")
      (node (ref "U1") (pin "54") (pinfunction "PD2_54") (pintype "bidirectional"))
    )
  )
)
